# LickSensor-2ch.net
KiCad netlist of a schematic drawn in EAGLE
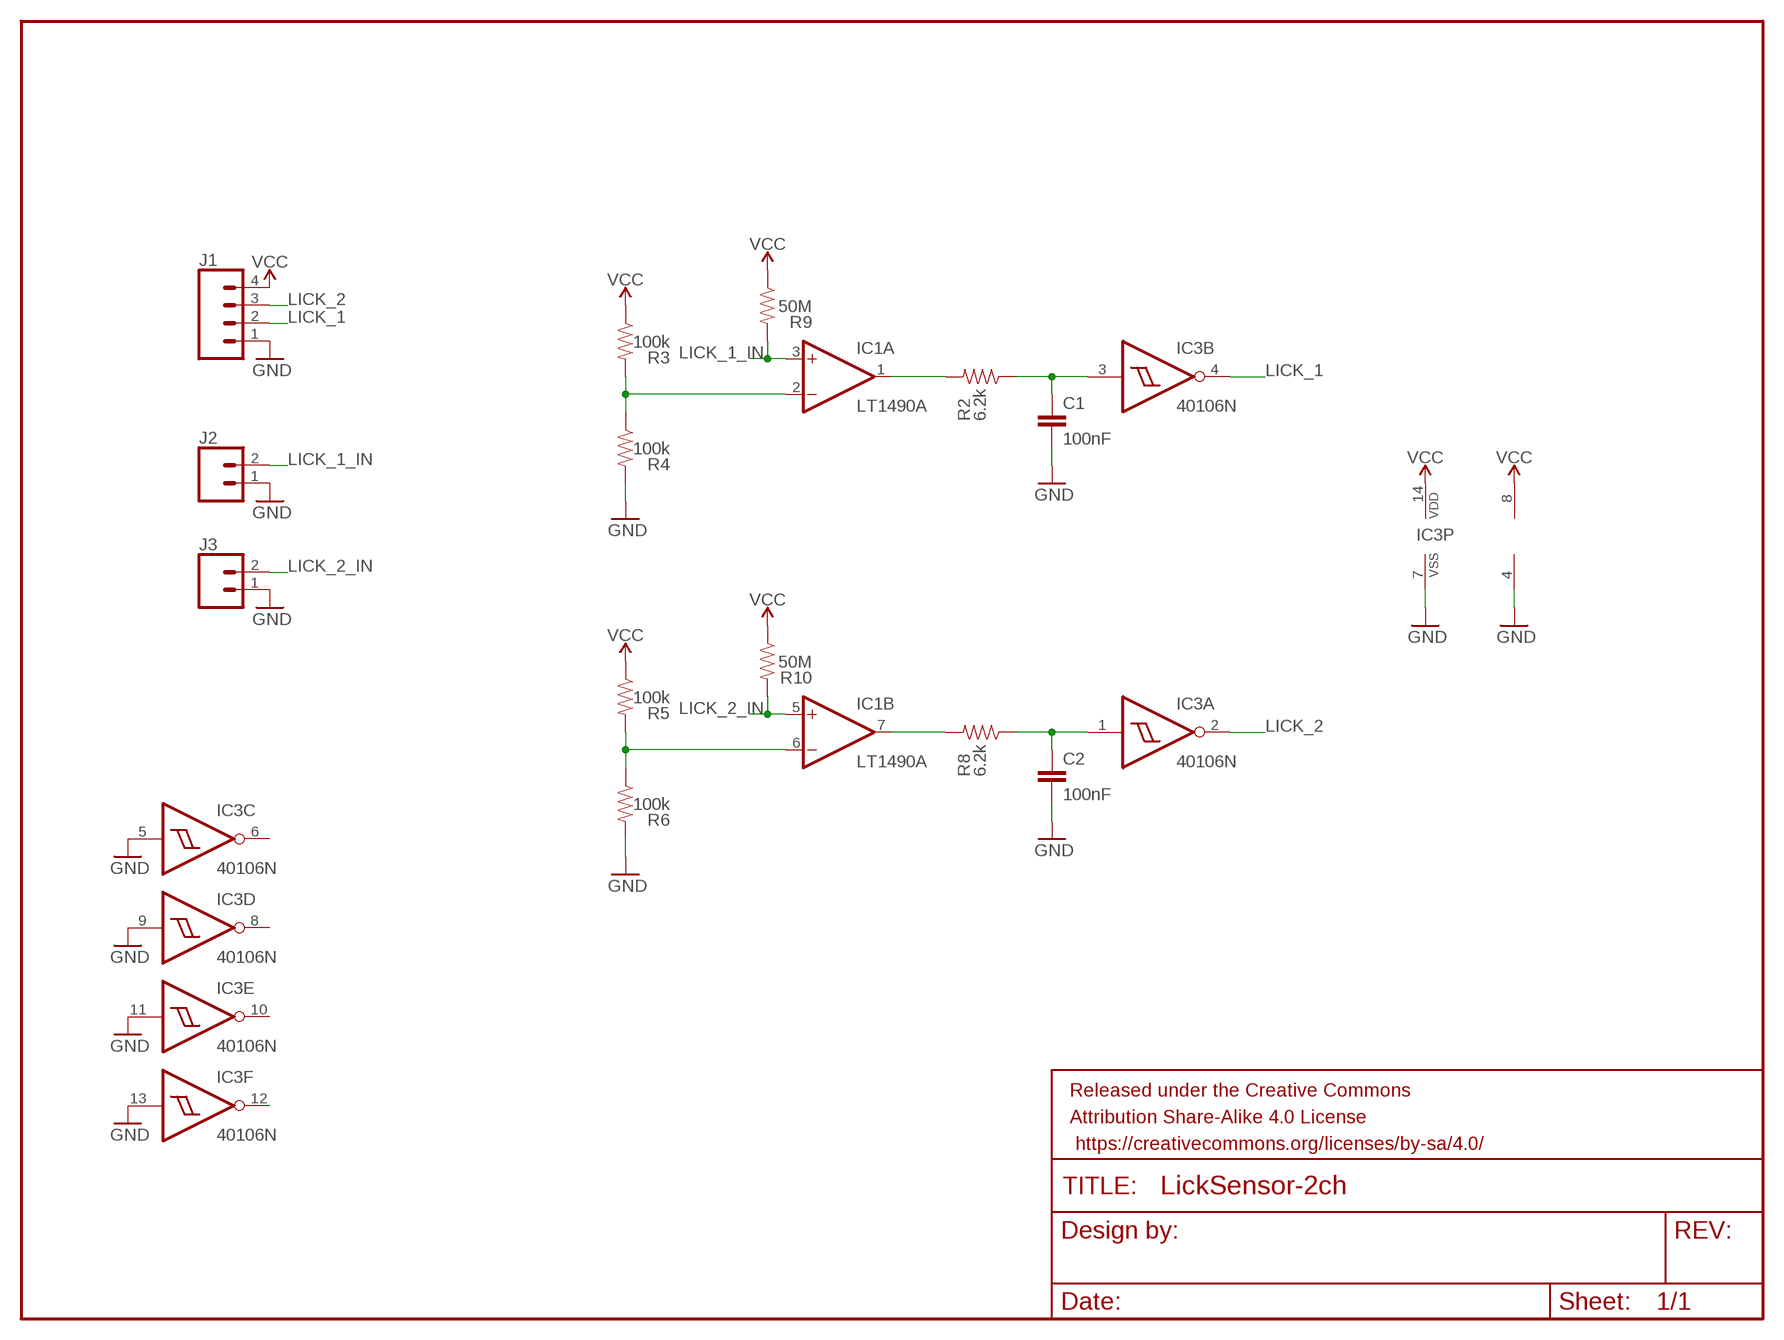
[diagram p0: schematic, sheet 1]

(export (version "E")
  (design (tool "Eeschema 10.0.6"))
  (components
    (comp (ref "C1")
      (value "100nF")
      (footprint "eagle-import:C5B3")
      (libsource (lib "eagle-import") (part "C5/3"))
    )
    (comp (ref "C2")
      (value "100nF")
      (footprint "eagle-import:C5B3")
      (libsource (lib "eagle-import") (part "C5/3"))
    )
    (comp (ref "FRAME1")
      (value "FRAME-LETTER")
      (footprint "eagle-import:CREATIVE_COMMONS")
      (libsource (lib "eagle-import") (part "FRAME-LETTER"))
    )
    (comp (ref "IC1")
      (value "LT1490A")
      (footprint "eagle-import:DIL08")
      (libsource (lib "eagle-import") (part "OPA2277P"))
    )
    (comp (ref "IC3")
      (value "40106N")
      (footprint "eagle-import:DIL14")
      (libsource (lib "eagle-import") (part "40106N"))
    )
    (comp (ref "J1")
      (value "CONN_04")
      (footprint "eagle-import:1X04")
      (libsource (lib "eagle-import") (part "CONN_04"))
    )
    (comp (ref "J2")
      (value "CONN_02")
      (footprint "eagle-import:1X02")
      (libsource (lib "eagle-import") (part "CONN_02"))
    )
    (comp (ref "J3")
      (value "CONN_02")
      (footprint "eagle-import:1X02")
      (libsource (lib "eagle-import") (part "CONN_02"))
    )
    (comp (ref "R2")
      (value "6.2k")
      (footprint "eagle-import:AXIAL-0.5")
      (libsource (lib "eagle-import") (part "RESISTORPTH-1/2W"))
    )
    (comp (ref "R3")
      (value "100k")
      (footprint "eagle-import:AXIAL-0.5")
      (libsource (lib "eagle-import") (part "RESISTORPTH-1/2W"))
    )
    (comp (ref "R4")
      (value "100k")
      (footprint "eagle-import:AXIAL-0.5")
      (libsource (lib "eagle-import") (part "RESISTORPTH-1/2W"))
    )
    (comp (ref "R5")
      (value "100k")
      (footprint "eagle-import:AXIAL-0.5")
      (libsource (lib "eagle-import") (part "RESISTORPTH-1/2W"))
    )
    (comp (ref "R6")
      (value "100k")
      (footprint "eagle-import:AXIAL-0.5")
      (libsource (lib "eagle-import") (part "RESISTORPTH-1/2W"))
    )
    (comp (ref "R8")
      (value "6.2k")
      (footprint "eagle-import:AXIAL-0.5")
      (libsource (lib "eagle-import") (part "RESISTORPTH-1/2W"))
    )
    (comp (ref "R9")
      (value "50M")
      (footprint "eagle-import:AXIAL-0.5")
      (libsource (lib "eagle-import") (part "RESISTORPTH-1/2W"))
    )
    (comp (ref "R10")
      (value "50M")
      (footprint "eagle-import:AXIAL-0.5")
      (libsource (lib "eagle-import") (part "RESISTORPTH-1/2W"))
    )
  )
  (nets
    (net (code "1") (name "/LICK_1") (class "Default")
      (node (ref "IC3") (pin "4") (pinfunction "O_4") (pintype "output"))
      (node (ref "J1") (pin "2") (pinfunction "2_2") (pintype "passive"))
    )
    (net (code "2") (name "/LICK_1_IN") (class "Default")
      (node (ref "IC1") (pin "3") (pinfunction "+IN_3") (pintype "input"))
      (node (ref "J2") (pin "2") (pinfunction "2_2") (pintype "passive"))
      (node (ref "R9") (pin "P$2") (pinfunction "2_P$2") (pintype "passive"))
    )
    (net (code "3") (name "/LICK_2") (class "Default")
      (node (ref "IC3") (pin "2") (pinfunction "O_2") (pintype "output"))
      (node (ref "J1") (pin "3") (pinfunction "3_3") (pintype "passive"))
    )
    (net (code "4") (name "/LICK_2_IN") (class "Default")
      (node (ref "IC1") (pin "5") (pinfunction "+IN_5") (pintype "input"))
      (node (ref "J3") (pin "2") (pinfunction "2_2") (pintype "passive"))
      (node (ref "R10") (pin "P$2") (pinfunction "2_P$2") (pintype "passive"))
    )
    (net (code "5") (name "GND") (class "Default")
      (node (ref "C1") (pin "2") (pinfunction "2_2") (pintype "passive"))
      (node (ref "C2") (pin "2") (pinfunction "2_2") (pintype "passive"))
      (node (ref "IC1") (pin "4") (pinfunction "V-_4") (pintype "power_in"))
      (node (ref "IC3") (pin "11") (pinfunction "I_11") (pintype "input"))
      (node (ref "IC3") (pin "13") (pinfunction "I_13") (pintype "input"))
      (node (ref "IC3") (pin "5") (pinfunction "I_5") (pintype "input"))
      (node (ref "IC3") (pin "7") (pinfunction "VSS_7") (pintype "power_in"))
      (node (ref "IC3") (pin "9") (pinfunction "I_9") (pintype "input"))
      (node (ref "J1") (pin "1") (pinfunction "1_1") (pintype "passive"))
      (node (ref "J2") (pin "1") (pinfunction "1_1") (pintype "passive"))
      (node (ref "J3") (pin "1") (pinfunction "1_1") (pintype "passive"))
      (node (ref "R4") (pin "P$2") (pinfunction "2_P$2") (pintype "passive"))
      (node (ref "R6") (pin "P$2") (pinfunction "2_P$2") (pintype "passive"))
    )
    (net (code "6") (name "Net-(IC1A--IN)") (class "Default")
      (node (ref "IC1") (pin "2") (pinfunction "-IN_2") (pintype "input"))
      (node (ref "R3") (pin "P$2") (pinfunction "2_P$2") (pintype "passive"))
      (node (ref "R4") (pin "P$1") (pinfunction "1_P$1") (pintype "passive"))
    )
    (net (code "7") (name "Net-(IC1A-OUT)") (class "Default")
      (node (ref "IC1") (pin "1") (pinfunction "OUT_1") (pintype "output"))
      (node (ref "R2") (pin "P$2") (pinfunction "2_P$2") (pintype "passive"))
    )
    (net (code "8") (name "Net-(IC1B--IN)") (class "Default")
      (node (ref "IC1") (pin "6") (pinfunction "-IN_6") (pintype "input"))
      (node (ref "R5") (pin "P$2") (pinfunction "2_P$2") (pintype "passive"))
      (node (ref "R6") (pin "P$1") (pinfunction "1_P$1") (pintype "passive"))
    )
    (net (code "9") (name "Net-(IC1B-OUT)") (class "Default")
      (node (ref "IC1") (pin "7") (pinfunction "OUT_7") (pintype "output"))
      (node (ref "R8") (pin "P$2") (pinfunction "2_P$2") (pintype "passive"))
    )
    (net (code "10") (name "Net-(IC3A-I)") (class "Default")
      (node (ref "C2") (pin "1") (pinfunction "1_1") (pintype "passive"))
      (node (ref "IC3") (pin "1") (pinfunction "I_1") (pintype "input"))
      (node (ref "R8") (pin "P$1") (pinfunction "1_P$1") (pintype "passive"))
    )
    (net (code "11") (name "Net-(IC3B-I)") (class "Default")
      (node (ref "C1") (pin "1") (pinfunction "1_1") (pintype "passive"))
      (node (ref "IC3") (pin "3") (pinfunction "I_3") (pintype "input"))
      (node (ref "R2") (pin "P$1") (pinfunction "1_P$1") (pintype "passive"))
    )
    (net (code "12") (name "VCC") (class "Default")
      (node (ref "IC1") (pin "8") (pinfunction "V+_8") (pintype "power_in"))
      (node (ref "IC3") (pin "14") (pinfunction "VDD_14") (pintype "power_in"))
      (node (ref "J1") (pin "4") (pinfunction "4_4") (pintype "passive"))
      (node (ref "R10") (pin "P$1") (pinfunction "1_P$1") (pintype "passive"))
      (node (ref "R3") (pin "P$1") (pinfunction "1_P$1") (pintype "passive"))
      (node (ref "R5") (pin "P$1") (pinfunction "1_P$1") (pintype "passive"))
      (node (ref "R9") (pin "P$1") (pinfunction "1_P$1") (pintype "passive"))
    )
    (net (code "13") (name "unconnected-(IC3C-O-Pad6)") (class "Default")
      (node (ref "IC3") (pin "6") (pinfunction "O_6") (pintype "output"))
    )
    (net (code "14") (name "unconnected-(IC3D-O-Pad8)") (class "Default")
      (node (ref "IC3") (pin "8") (pinfunction "O_8") (pintype "output"))
    )
    (net (code "15") (name "unconnected-(IC3E-O-Pad10)") (class "Default")
      (node (ref "IC3") (pin "10") (pinfunction "O_10") (pintype "output"))
    )
    (net (code "16") (name "unconnected-(IC3F-O-Pad12)") (class "Default")
      (node (ref "IC3") (pin "12") (pinfunction "O_12") (pintype "output"))
    )
  )
)
